# GND.net
KiCad netlist of a schematic drawn in Altium Designer
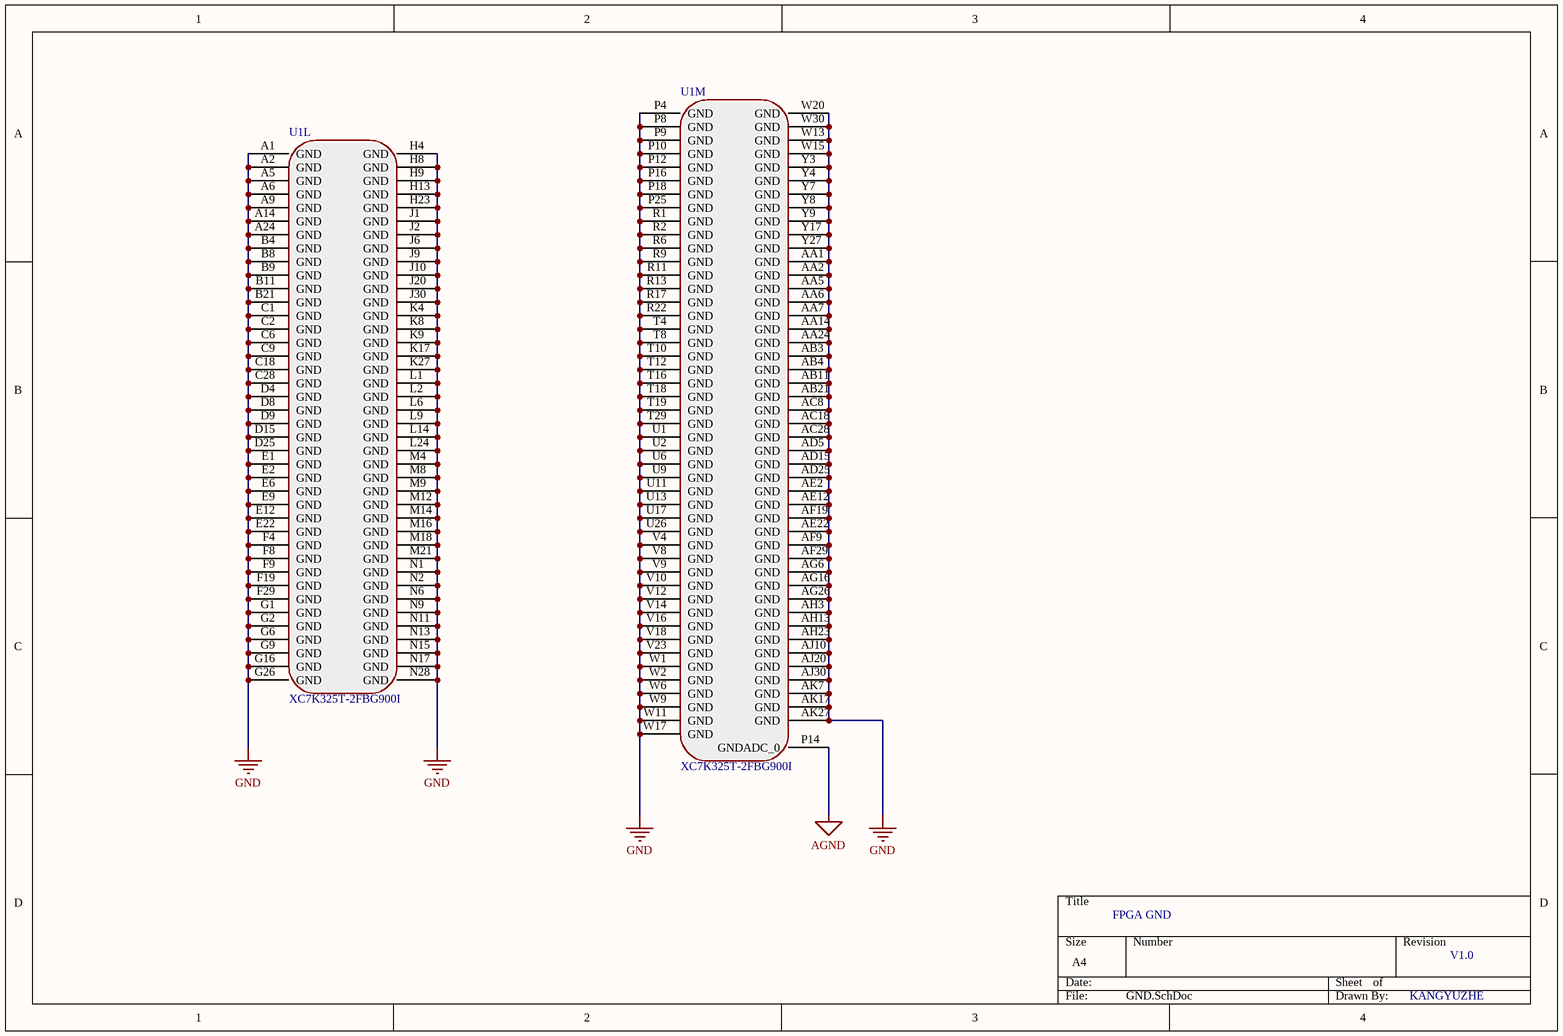
[diagram p0: GND.SchDoc]

(export (version "E")
  (design (tool "Eeschema 10.0.6"))
  (components
    (comp (ref "U1")
      (value "XC7K325T-2FBG900I")
      (footprint "FBG900")
      (libsource (lib "Schlib1") (part "XC7K325T-2FBG900I"))
    )
  )
  (nets
    (net (code "1") (name "AGND") (class "Default")
      (node (ref "U1") (pin "P14") (pinfunction "GNDADC_0_P14") (pintype "passive"))
    )
    (net (code "2") (name "GND") (class "Default")
      (node (ref "U1") (pin "A1") (pinfunction "GND_A1") (pintype "passive"))
      (node (ref "U1") (pin "A14") (pinfunction "GND_A14") (pintype "passive"))
      (node (ref "U1") (pin "A2") (pinfunction "GND_A2") (pintype "passive"))
      (node (ref "U1") (pin "A24") (pinfunction "GND_A24") (pintype "passive"))
      (node (ref "U1") (pin "A5") (pinfunction "GND_A5") (pintype "passive"))
      (node (ref "U1") (pin "A6") (pinfunction "GND_A6") (pintype "passive"))
      (node (ref "U1") (pin "A9") (pinfunction "GND_A9") (pintype "passive"))
      (node (ref "U1") (pin "AA1") (pinfunction "GND_AA1") (pintype "passive"))
      (node (ref "U1") (pin "AA14") (pinfunction "GND_AA14") (pintype "passive"))
      (node (ref "U1") (pin "AA2") (pinfunction "GND_AA2") (pintype "passive"))
      (node (ref "U1") (pin "AA24") (pinfunction "GND_AA24") (pintype "passive"))
      (node (ref "U1") (pin "AA5") (pinfunction "GND_AA5") (pintype "passive"))
      (node (ref "U1") (pin "AA6") (pinfunction "GND_AA6") (pintype "passive"))
      (node (ref "U1") (pin "AA7") (pinfunction "GND_AA7") (pintype "passive"))
      (node (ref "U1") (pin "AB11") (pinfunction "GND_AB11") (pintype "passive"))
      (node (ref "U1") (pin "AB21") (pinfunction "GND_AB21") (pintype "passive"))
      (node (ref "U1") (pin "AB3") (pinfunction "GND_AB3") (pintype "passive"))
      (node (ref "U1") (pin "AB4") (pinfunction "GND_AB4") (pintype "passive"))
      (node (ref "U1") (pin "AC18") (pinfunction "GND_AC18") (pintype "passive"))
      (node (ref "U1") (pin "AC28") (pinfunction "GND_AC28") (pintype "passive"))
      (node (ref "U1") (pin "AC8") (pinfunction "GND_AC8") (pintype "passive"))
      (node (ref "U1") (pin "AD15") (pinfunction "GND_AD15") (pintype "passive"))
      (node (ref "U1") (pin "AD25") (pinfunction "GND_AD25") (pintype "passive"))
      (node (ref "U1") (pin "AD5") (pinfunction "GND_AD5") (pintype "passive"))
      (node (ref "U1") (pin "AE12") (pinfunction "GND_AE12") (pintype "passive"))
      (node (ref "U1") (pin "AE2") (pinfunction "GND_AE2") (pintype "passive"))
      (node (ref "U1") (pin "AE22") (pinfunction "GND_AE22") (pintype "passive"))
      (node (ref "U1") (pin "AF19") (pinfunction "GND_AF19") (pintype "passive"))
      (node (ref "U1") (pin "AF29") (pinfunction "GND_AF29") (pintype "passive"))
      (node (ref "U1") (pin "AF9") (pinfunction "GND_AF9") (pintype "passive"))
      (node (ref "U1") (pin "AG16") (pinfunction "GND_AG16") (pintype "passive"))
      (node (ref "U1") (pin "AG26") (pinfunction "GND_AG26") (pintype "passive"))
      (node (ref "U1") (pin "AG6") (pinfunction "GND_AG6") (pintype "passive"))
      (node (ref "U1") (pin "AH13") (pinfunction "GND_AH13") (pintype "passive"))
      (node (ref "U1") (pin "AH23") (pinfunction "GND_AH23") (pintype "passive"))
      (node (ref "U1") (pin "AH3") (pinfunction "GND_AH3") (pintype "passive"))
      (node (ref "U1") (pin "AJ10") (pinfunction "GND_AJ10") (pintype "passive"))
      (node (ref "U1") (pin "AJ20") (pinfunction "GND_AJ20") (pintype "passive"))
      (node (ref "U1") (pin "AJ30") (pinfunction "GND_AJ30") (pintype "passive"))
      (node (ref "U1") (pin "AK17") (pinfunction "GND_AK17") (pintype "passive"))
      (node (ref "U1") (pin "AK27") (pinfunction "GND_AK27") (pintype "passive"))
      (node (ref "U1") (pin "AK7") (pinfunction "GND_AK7") (pintype "passive"))
      (node (ref "U1") (pin "B11") (pinfunction "GND_B11") (pintype "passive"))
      (node (ref "U1") (pin "B21") (pinfunction "GND_B21") (pintype "passive"))
      (node (ref "U1") (pin "B4") (pinfunction "GND_B4") (pintype "passive"))
      (node (ref "U1") (pin "B8") (pinfunction "GND_B8") (pintype "passive"))
      (node (ref "U1") (pin "B9") (pinfunction "GND_B9") (pintype "passive"))
      (node (ref "U1") (pin "C1") (pinfunction "GND_C1") (pintype "passive"))
      (node (ref "U1") (pin "C18") (pinfunction "GND_C18") (pintype "passive"))
      (node (ref "U1") (pin "C2") (pinfunction "GND_C2") (pintype "passive"))
      (node (ref "U1") (pin "C28") (pinfunction "GND_C28") (pintype "passive"))
      (node (ref "U1") (pin "C6") (pinfunction "GND_C6") (pintype "passive"))
      (node (ref "U1") (pin "C9") (pinfunction "GND_C9") (pintype "passive"))
      (node (ref "U1") (pin "D15") (pinfunction "GND_D15") (pintype "passive"))
      (node (ref "U1") (pin "D25") (pinfunction "GND_D25") (pintype "passive"))
      (node (ref "U1") (pin "D4") (pinfunction "GND_D4") (pintype "passive"))
      (node (ref "U1") (pin "D8") (pinfunction "GND_D8") (pintype "passive"))
      (node (ref "U1") (pin "D9") (pinfunction "GND_D9") (pintype "passive"))
      (node (ref "U1") (pin "E1") (pinfunction "GND_E1") (pintype "passive"))
      (node (ref "U1") (pin "E12") (pinfunction "GND_E12") (pintype "passive"))
      (node (ref "U1") (pin "E2") (pinfunction "GND_E2") (pintype "passive"))
      (node (ref "U1") (pin "E22") (pinfunction "GND_E22") (pintype "passive"))
      (node (ref "U1") (pin "E6") (pinfunction "GND_E6") (pintype "passive"))
      (node (ref "U1") (pin "E9") (pinfunction "GND_E9") (pintype "passive"))
      (node (ref "U1") (pin "F19") (pinfunction "GND_F19") (pintype "passive"))
      (node (ref "U1") (pin "F29") (pinfunction "GND_F29") (pintype "passive"))
      (node (ref "U1") (pin "F4") (pinfunction "GND_F4") (pintype "passive"))
      (node (ref "U1") (pin "F8") (pinfunction "GND_F8") (pintype "passive"))
      (node (ref "U1") (pin "F9") (pinfunction "GND_F9") (pintype "passive"))
      (node (ref "U1") (pin "G1") (pinfunction "GND_G1") (pintype "passive"))
      (node (ref "U1") (pin "G16") (pinfunction "GND_G16") (pintype "passive"))
      (node (ref "U1") (pin "G2") (pinfunction "GND_G2") (pintype "passive"))
      (node (ref "U1") (pin "G26") (pinfunction "GND_G26") (pintype "passive"))
      (node (ref "U1") (pin "G6") (pinfunction "GND_G6") (pintype "passive"))
      (node (ref "U1") (pin "G9") (pinfunction "GND_G9") (pintype "passive"))
      (node (ref "U1") (pin "H13") (pinfunction "GND_H13") (pintype "passive"))
      (node (ref "U1") (pin "H23") (pinfunction "GND_H23") (pintype "passive"))
      (node (ref "U1") (pin "H4") (pinfunction "GND_H4") (pintype "passive"))
      (node (ref "U1") (pin "H8") (pinfunction "GND_H8") (pintype "passive"))
      (node (ref "U1") (pin "H9") (pinfunction "GND_H9") (pintype "passive"))
      (node (ref "U1") (pin "J1") (pinfunction "GND_J1") (pintype "passive"))
      (node (ref "U1") (pin "J10") (pinfunction "GND_J10") (pintype "passive"))
      (node (ref "U1") (pin "J2") (pinfunction "GND_J2") (pintype "passive"))
      (node (ref "U1") (pin "J20") (pinfunction "GND_J20") (pintype "passive"))
      (node (ref "U1") (pin "J30") (pinfunction "GND_J30") (pintype "passive"))
      (node (ref "U1") (pin "J6") (pinfunction "GND_J6") (pintype "passive"))
      (node (ref "U1") (pin "J9") (pinfunction "GND_J9") (pintype "passive"))
      (node (ref "U1") (pin "K17") (pinfunction "GND_K17") (pintype "passive"))
      (node (ref "U1") (pin "K27") (pinfunction "GND_K27") (pintype "passive"))
      (node (ref "U1") (pin "K4") (pinfunction "GND_K4") (pintype "passive"))
      (node (ref "U1") (pin "K8") (pinfunction "GND_K8") (pintype "passive"))
      (node (ref "U1") (pin "K9") (pinfunction "GND_K9") (pintype "passive"))
      (node (ref "U1") (pin "L1") (pinfunction "GND_L1") (pintype "passive"))
      (node (ref "U1") (pin "L14") (pinfunction "GND_L14") (pintype "passive"))
      (node (ref "U1") (pin "L2") (pinfunction "GND_L2") (pintype "passive"))
      (node (ref "U1") (pin "L24") (pinfunction "GND_L24") (pintype "passive"))
      (node (ref "U1") (pin "L6") (pinfunction "GND_L6") (pintype "passive"))
      (node (ref "U1") (pin "L9") (pinfunction "GND_L9") (pintype "passive"))
      (node (ref "U1") (pin "M12") (pinfunction "GND_M12") (pintype "passive"))
      (node (ref "U1") (pin "M14") (pinfunction "GND_M14") (pintype "passive"))
      (node (ref "U1") (pin "M16") (pinfunction "GND_M16") (pintype "passive"))
      (node (ref "U1") (pin "M18") (pinfunction "GND_M18") (pintype "passive"))
      (node (ref "U1") (pin "M21") (pinfunction "GND_M21") (pintype "passive"))
      (node (ref "U1") (pin "M4") (pinfunction "GND_M4") (pintype "passive"))
      (node (ref "U1") (pin "M8") (pinfunction "GND_M8") (pintype "passive"))
      (node (ref "U1") (pin "M9") (pinfunction "GND_M9") (pintype "passive"))
      (node (ref "U1") (pin "N1") (pinfunction "GND_N1") (pintype "passive"))
      (node (ref "U1") (pin "N11") (pinfunction "GND_N11") (pintype "passive"))
      (node (ref "U1") (pin "N13") (pinfunction "GND_N13") (pintype "passive"))
      (node (ref "U1") (pin "N15") (pinfunction "GND_N15") (pintype "passive"))
      (node (ref "U1") (pin "N17") (pinfunction "GND_N17") (pintype "passive"))
      (node (ref "U1") (pin "N2") (pinfunction "GND_N2") (pintype "passive"))
      (node (ref "U1") (pin "N28") (pinfunction "GND_N28") (pintype "passive"))
      (node (ref "U1") (pin "N6") (pinfunction "GND_N6") (pintype "passive"))
      (node (ref "U1") (pin "N9") (pinfunction "GND_N9") (pintype "passive"))
      (node (ref "U1") (pin "P10") (pinfunction "GND_P10") (pintype "passive"))
      (node (ref "U1") (pin "P12") (pinfunction "GND_P12") (pintype "passive"))
      (node (ref "U1") (pin "P16") (pinfunction "GND_P16") (pintype "passive"))
      (node (ref "U1") (pin "P18") (pinfunction "GND_P18") (pintype "passive"))
      (node (ref "U1") (pin "P25") (pinfunction "GND_P25") (pintype "passive"))
      (node (ref "U1") (pin "P4") (pinfunction "GND_P4") (pintype "passive"))
      (node (ref "U1") (pin "P8") (pinfunction "GND_P8") (pintype "passive"))
      (node (ref "U1") (pin "P9") (pinfunction "GND_P9") (pintype "passive"))
      (node (ref "U1") (pin "R1") (pinfunction "GND_R1") (pintype "passive"))
      (node (ref "U1") (pin "R11") (pinfunction "GND_R11") (pintype "passive"))
      (node (ref "U1") (pin "R13") (pinfunction "GND_R13") (pintype "passive"))
      (node (ref "U1") (pin "R17") (pinfunction "GND_R17") (pintype "passive"))
      (node (ref "U1") (pin "R2") (pinfunction "GND_R2") (pintype "passive"))
      (node (ref "U1") (pin "R22") (pinfunction "GND_R22") (pintype "passive"))
      (node (ref "U1") (pin "R6") (pinfunction "GND_R6") (pintype "passive"))
      (node (ref "U1") (pin "R9") (pinfunction "GND_R9") (pintype "passive"))
      (node (ref "U1") (pin "T10") (pinfunction "GND_T10") (pintype "passive"))
      (node (ref "U1") (pin "T12") (pinfunction "GND_T12") (pintype "passive"))
      (node (ref "U1") (pin "T16") (pinfunction "GND_T16") (pintype "passive"))
      (node (ref "U1") (pin "T18") (pinfunction "GND_T18") (pintype "passive"))
      (node (ref "U1") (pin "T19") (pinfunction "GND_T19") (pintype "passive"))
      (node (ref "U1") (pin "T29") (pinfunction "GND_T29") (pintype "passive"))
      (node (ref "U1") (pin "T4") (pinfunction "GND_T4") (pintype "passive"))
      (node (ref "U1") (pin "T8") (pinfunction "GND_T8") (pintype "passive"))
      (node (ref "U1") (pin "U1") (pinfunction "GND_U1") (pintype "passive"))
      (node (ref "U1") (pin "U11") (pinfunction "GND_U11") (pintype "passive"))
      (node (ref "U1") (pin "U13") (pinfunction "GND_U13") (pintype "passive"))
      (node (ref "U1") (pin "U17") (pinfunction "GND_U17") (pintype "passive"))
      (node (ref "U1") (pin "U2") (pinfunction "GND_U2") (pintype "passive"))
      (node (ref "U1") (pin "U26") (pinfunction "GND_U26") (pintype "passive"))
      (node (ref "U1") (pin "U6") (pinfunction "GND_U6") (pintype "passive"))
      (node (ref "U1") (pin "U9") (pinfunction "GND_U9") (pintype "passive"))
      (node (ref "U1") (pin "V10") (pinfunction "GND_V10") (pintype "passive"))
      (node (ref "U1") (pin "V12") (pinfunction "GND_V12") (pintype "passive"))
      (node (ref "U1") (pin "V14") (pinfunction "GND_V14") (pintype "passive"))
      (node (ref "U1") (pin "V16") (pinfunction "GND_V16") (pintype "passive"))
      (node (ref "U1") (pin "V18") (pinfunction "GND_V18") (pintype "passive"))
      (node (ref "U1") (pin "V23") (pinfunction "GND_V23") (pintype "passive"))
      (node (ref "U1") (pin "V4") (pinfunction "GND_V4") (pintype "passive"))
      (node (ref "U1") (pin "V8") (pinfunction "GND_V8") (pintype "passive"))
      (node (ref "U1") (pin "V9") (pinfunction "GND_V9") (pintype "passive"))
      (node (ref "U1") (pin "W1") (pinfunction "GND_W1") (pintype "passive"))
      (node (ref "U1") (pin "W11") (pinfunction "GND_W11") (pintype "passive"))
      (node (ref "U1") (pin "W13") (pinfunction "GND_W13") (pintype "passive"))
      (node (ref "U1") (pin "W15") (pinfunction "GND_W15") (pintype "passive"))
      (node (ref "U1") (pin "W17") (pinfunction "GND_W17") (pintype "passive"))
      (node (ref "U1") (pin "W2") (pinfunction "GND_W2") (pintype "passive"))
      (node (ref "U1") (pin "W20") (pinfunction "GND_W20") (pintype "passive"))
      (node (ref "U1") (pin "W30") (pinfunction "GND_W30") (pintype "passive"))
      (node (ref "U1") (pin "W6") (pinfunction "GND_W6") (pintype "passive"))
      (node (ref "U1") (pin "W9") (pinfunction "GND_W9") (pintype "passive"))
      (node (ref "U1") (pin "Y17") (pinfunction "GND_Y17") (pintype "passive"))
      (node (ref "U1") (pin "Y27") (pinfunction "GND_Y27") (pintype "passive"))
      (node (ref "U1") (pin "Y3") (pinfunction "GND_Y3") (pintype "passive"))
      (node (ref "U1") (pin "Y4") (pinfunction "GND_Y4") (pintype "passive"))
      (node (ref "U1") (pin "Y7") (pinfunction "GND_Y7") (pintype "passive"))
      (node (ref "U1") (pin "Y8") (pinfunction "GND_Y8") (pintype "passive"))
      (node (ref "U1") (pin "Y9") (pinfunction "GND_Y9") (pintype "passive"))
    )
  )
)
